# bga_test.net
KiCad netlist of a schematic drawn in EAGLE
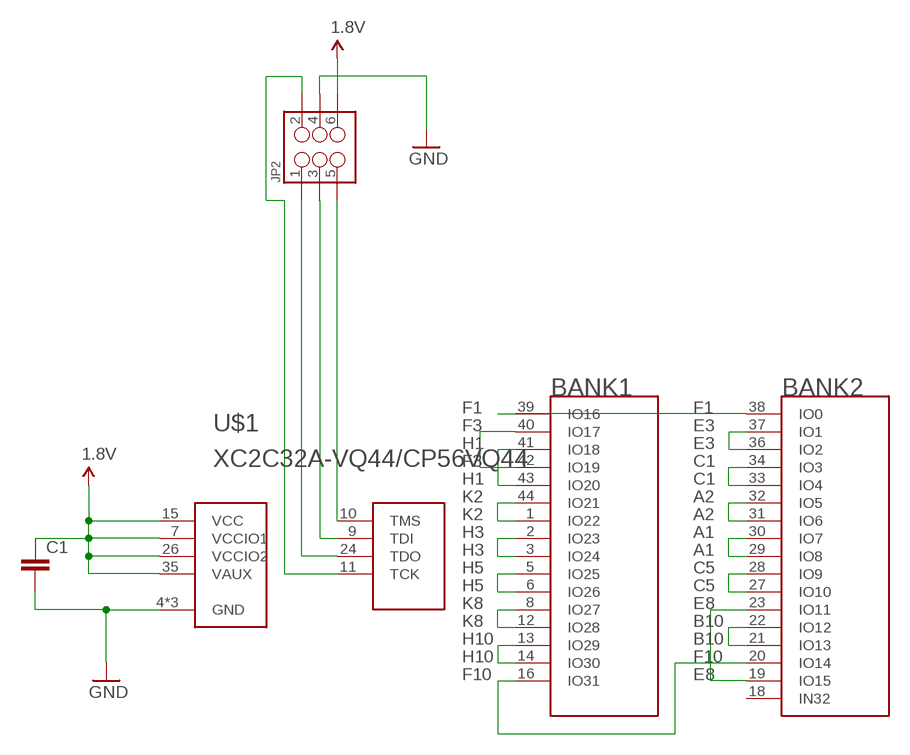
[diagram p0: schematic, sheet 1]

(export (version "E")
  (design (tool "Eeschema 10.0.6"))
  (components
    (comp (ref "C1")
      (value "CAP0402-CAP")
      (footprint "eagle-import:0402-CAP")
      (libsource (lib "eagle-import") (part "CAP0402-CAP"))
    )
    (comp (ref "JP2")
      (value "M03X2NO_SILK")
      (footprint "eagle-import:2X3-NS")
      (libsource (lib "eagle-import") (part "M03X2NO_SILK"))
    )
    (comp (ref "U$1")
      (value "XC2C32A-VQ44/CP56VQ44")
      (footprint "eagle-import:XILINX_VQ44")
      (libsource (lib "eagle-import") (part "XC2C32A-VQ44/CP56VQ44"))
    )
  )
  (nets
    (net (code "1") (name "/A1") (class "Default")
      (node (ref "U$1") (pin "29") (pinfunction "IO8_29") (pintype "bidirectional"))
      (node (ref "U$1") (pin "30") (pinfunction "IO7_30") (pintype "bidirectional"))
    )
    (net (code "2") (name "/A2") (class "Default")
      (node (ref "U$1") (pin "31") (pinfunction "IO6_31") (pintype "bidirectional"))
      (node (ref "U$1") (pin "32") (pinfunction "IO5_32") (pintype "bidirectional"))
    )
    (net (code "3") (name "/B10") (class "Default")
      (node (ref "U$1") (pin "21") (pinfunction "IO13_21") (pintype "bidirectional"))
      (node (ref "U$1") (pin "22") (pinfunction "IO12_22") (pintype "bidirectional"))
    )
    (net (code "4") (name "/C1") (class "Default")
      (node (ref "U$1") (pin "33") (pinfunction "IO4_33") (pintype "bidirectional"))
      (node (ref "U$1") (pin "34") (pinfunction "IO3_34") (pintype "bidirectional"))
    )
    (net (code "5") (name "/C5") (class "Default")
      (node (ref "U$1") (pin "27") (pinfunction "IO10_27") (pintype "bidirectional"))
      (node (ref "U$1") (pin "28") (pinfunction "IO9_28") (pintype "bidirectional"))
    )
    (net (code "6") (name "/E3") (class "Default")
      (node (ref "U$1") (pin "36") (pinfunction "IO2_36") (pintype "bidirectional"))
      (node (ref "U$1") (pin "37") (pinfunction "IO1_37") (pintype "bidirectional"))
    )
    (net (code "7") (name "/E8") (class "Default")
      (node (ref "U$1") (pin "19") (pinfunction "IO15_19") (pintype "bidirectional"))
      (node (ref "U$1") (pin "23") (pinfunction "IO11_23") (pintype "bidirectional"))
    )
    (net (code "8") (name "/F1") (class "Default")
      (node (ref "U$1") (pin "38") (pinfunction "IO0_38") (pintype "bidirectional"))
      (node (ref "U$1") (pin "39") (pinfunction "IO16_39") (pintype "bidirectional"))
    )
    (net (code "9") (name "/F3") (class "Default")
      (node (ref "U$1") (pin "40") (pinfunction "IO17_40") (pintype "bidirectional"))
      (node (ref "U$1") (pin "42") (pinfunction "IO19_42") (pintype "bidirectional"))
    )
    (net (code "10") (name "/F10") (class "Default")
      (node (ref "U$1") (pin "16") (pinfunction "IO31_16") (pintype "bidirectional"))
      (node (ref "U$1") (pin "20") (pinfunction "IO14_20") (pintype "bidirectional"))
    )
    (net (code "11") (name "/H1") (class "Default")
      (node (ref "U$1") (pin "41") (pinfunction "IO18_41") (pintype "bidirectional"))
      (node (ref "U$1") (pin "43") (pinfunction "IO20_43") (pintype "bidirectional"))
    )
    (net (code "12") (name "/H3") (class "Default")
      (node (ref "U$1") (pin "2") (pinfunction "IO23_2") (pintype "bidirectional"))
      (node (ref "U$1") (pin "3") (pinfunction "IO24_3") (pintype "bidirectional"))
    )
    (net (code "13") (name "/H5") (class "Default")
      (node (ref "U$1") (pin "5") (pinfunction "IO25_5") (pintype "bidirectional"))
      (node (ref "U$1") (pin "6") (pinfunction "IO26_6") (pintype "bidirectional"))
    )
    (net (code "14") (name "/H10") (class "Default")
      (node (ref "U$1") (pin "13") (pinfunction "IO29_13") (pintype "bidirectional"))
      (node (ref "U$1") (pin "14") (pinfunction "IO30_14") (pintype "bidirectional"))
    )
    (net (code "15") (name "/K2") (class "Default")
      (node (ref "U$1") (pin "1") (pinfunction "IO22_1") (pintype "bidirectional"))
      (node (ref "U$1") (pin "44") (pinfunction "IO21_44") (pintype "bidirectional"))
    )
    (net (code "16") (name "/K8") (class "Default")
      (node (ref "U$1") (pin "12") (pinfunction "IO28_12") (pintype "bidirectional"))
      (node (ref "U$1") (pin "8") (pinfunction "IO27_8") (pintype "bidirectional"))
    )
    (net (code "17") (name "1.8V") (class "Default")
      (node (ref "C1") (pin "1") (pinfunction "1_1") (pintype "passive"))
      (node (ref "JP2") (pin "6") (pinfunction "6_6") (pintype "bidirectional"))
      (node (ref "U$1") (pin "15") (pinfunction "VCC_15") (pintype "bidirectional"))
      (node (ref "U$1") (pin "26") (pinfunction "VCCIO2_26") (pintype "bidirectional"))
      (node (ref "U$1") (pin "35") (pinfunction "VAUX_35") (pintype "bidirectional"))
      (node (ref "U$1") (pin "7") (pinfunction "VCCIO1_7") (pintype "bidirectional"))
    )
    (net (code "18") (name "GND") (class "Default")
      (node (ref "C1") (pin "2") (pinfunction "2_2") (pintype "passive"))
      (node (ref "JP2") (pin "4") (pinfunction "4_4") (pintype "bidirectional"))
      (node (ref "U$1") (pin "17") (pinfunction "GND_17") (pintype "bidirectional"))
      (node (ref "U$1") (pin "25") (pinfunction "GND_25") (pintype "bidirectional"))
      (node (ref "U$1") (pin "4") (pinfunction "GND_4") (pintype "bidirectional"))
    )
    (net (code "19") (name "Net-(U$1-TCK)") (class "Default")
      (node (ref "JP2") (pin "2") (pinfunction "2_2") (pintype "bidirectional"))
      (node (ref "U$1") (pin "11") (pinfunction "TCK_11") (pintype "bidirectional"))
    )
    (net (code "20") (name "Net-(U$1-TDI)") (class "Default")
      (node (ref "JP2") (pin "3") (pinfunction "3_3") (pintype "bidirectional"))
      (node (ref "U$1") (pin "9") (pinfunction "TDI_9") (pintype "bidirectional"))
    )
    (net (code "21") (name "Net-(U$1-TDO)") (class "Default")
      (node (ref "JP2") (pin "1") (pinfunction "1_1") (pintype "bidirectional"))
      (node (ref "U$1") (pin "24") (pinfunction "TDO_24") (pintype "bidirectional"))
    )
    (net (code "22") (name "Net-(U$1-TMS)") (class "Default")
      (node (ref "JP2") (pin "5") (pinfunction "5_5") (pintype "bidirectional"))
      (node (ref "U$1") (pin "10") (pinfunction "TMS_10") (pintype "bidirectional"))
    )
    (net (code "23") (name "unconnected-(U$1-IN32-Pad18)") (class "Default")
      (node (ref "U$1") (pin "18") (pinfunction "IN32_18") (pintype "bidirectional"))
    )
  )
)
